# E17-04_ICS.net
KiCad netlist of a schematic drawn in Altium Designer
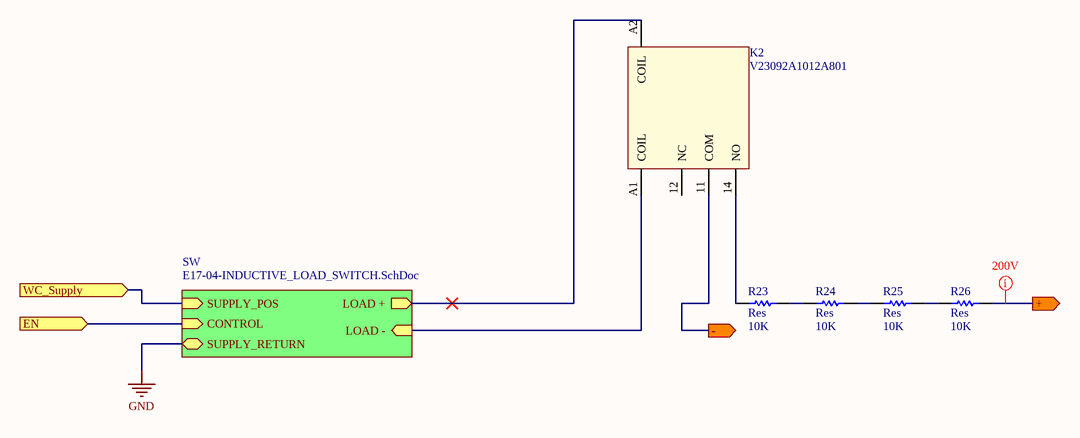
[diagram p0: E17-04_ICS.SchDoc]

(export (version "E")
  (design (tool "Eeschema 10.0.6"))
  (components
    (comp (ref "K2")
      (value "V23092A1012A801")
      (footprint "SCHRACK")
      (description "12V slim SPDT Relay")
      (fields (field (name "MFG") "TE") (field (name "MFG_PN") "V23092A1012A801"))
      (libsource (lib "Relays") (part "V23092A1012A801"))
    )
    (comp (ref "R23")
      (value "Res")
      (footprint "3216[1206]")
      (description "Surface Mount Resistor")
      (fields (field (name "ALTIUM_VALUE") "10K") (field (name "PUBLISHER") "Altium Limited"))
      (libsource (lib "Resistors") (part "Res"))
    )
    (comp (ref "R24")
      (value "Res")
      (footprint "3216[1206]")
      (description "Surface Mount Resistor")
      (fields (field (name "ALTIUM_VALUE") "10K") (field (name "PUBLISHER") "Altium Limited"))
      (libsource (lib "Resistors") (part "Res"))
    )
    (comp (ref "R25")
      (value "Res")
      (footprint "3216[1206]")
      (description "Surface Mount Resistor")
      (fields (field (name "ALTIUM_VALUE") "10K") (field (name "PUBLISHER") "Altium Limited"))
      (libsource (lib "Resistors") (part "Res"))
    )
    (comp (ref "R26")
      (value "Res")
      (footprint "3216[1206]")
      (description "Surface Mount Resistor")
      (fields (field (name "ALTIUM_VALUE") "10K") (field (name "PUBLISHER") "Altium Limited"))
      (libsource (lib "Resistors") (part "Res"))
    )
  )
  (nets
    (net (code "1") (name "/+") (class "Default")
      (node (ref "R26") (pin "2") (pinfunction "2_2") (pintype "passive"))
    )
    (net (code "2") (name "/-") (class "Default")
      (node (ref "K2") (pin "11") (pinfunction "COM_11") (pintype "passive"))
    )
    (net (code "4") (name "/LOAD +") (class "Default")
      (node (ref "K2") (pin "A2") (pinfunction "COIL_A2") (pintype "passive"))
    )
    (net (code "5") (name "/LOAD -") (class "Default")
      (node (ref "K2") (pin "A1") (pinfunction "COIL_A1") (pintype "passive"))
    )
    (net (code "8") (name "Net-(K2-NO)") (class "Default")
      (node (ref "K2") (pin "14") (pinfunction "NO_14") (pintype "passive"))
      (node (ref "R23") (pin "1") (pinfunction "1_1") (pintype "passive"))
    )
    (net (code "9") (name "Net-(R23-Pad2)") (class "Default")
      (node (ref "R23") (pin "2") (pinfunction "2_2") (pintype "passive"))
      (node (ref "R24") (pin "1") (pinfunction "1_1") (pintype "passive"))
    )
    (net (code "10") (name "Net-(R24-Pad2)") (class "Default")
      (node (ref "R24") (pin "2") (pinfunction "2_2") (pintype "passive"))
      (node (ref "R25") (pin "1") (pinfunction "1_1") (pintype "passive"))
    )
    (net (code "11") (name "Net-(R25-Pad2)") (class "Default")
      (node (ref "R25") (pin "2") (pinfunction "2_2") (pintype "passive"))
      (node (ref "R26") (pin "1") (pinfunction "1_1") (pintype "passive"))
    )
    (net (code "12") (name "unconnected-(K2-NC-Pad12)") (class "Default")
      (node (ref "K2") (pin "12") (pinfunction "NC_12") (pintype "passive"))
    )
  )
)
